# SensorBoard.net
KiCad netlist of a schematic drawn in EAGLE
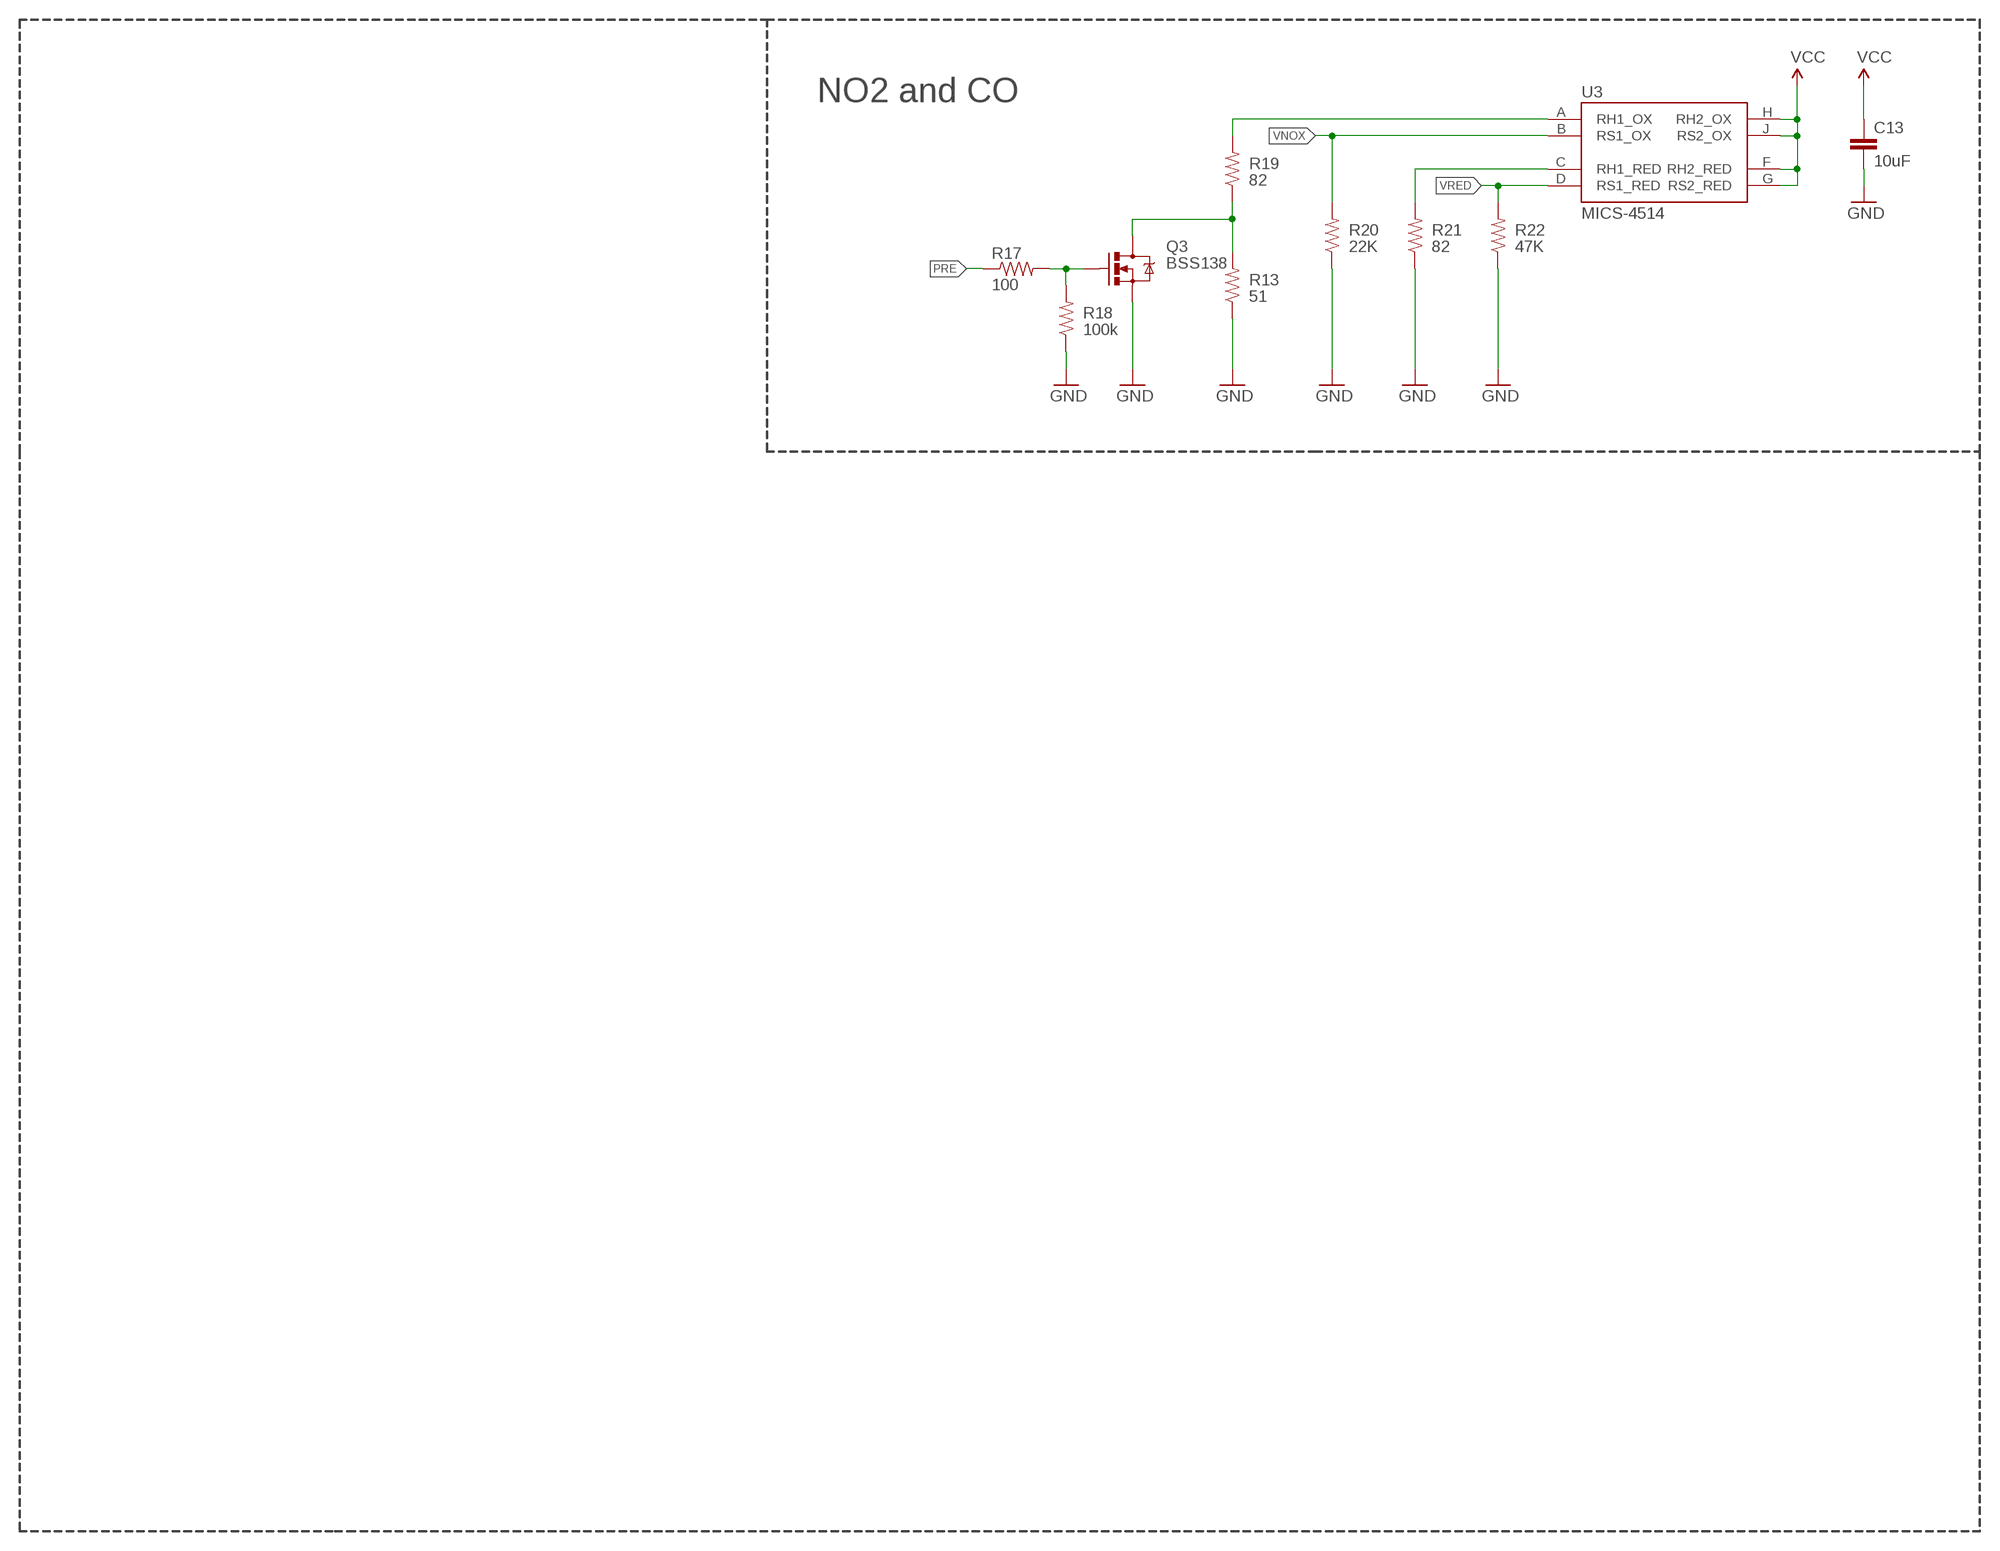
[diagram p0: schematic, sheet 1]

(export (version "E")
  (design (tool "Eeschema 10.0.6"))
  (components
    (comp (ref "C13")
      (value "10uF")
      (footprint "eagle-import:1206")
      (libsource (lib "eagle-import") (part "CAP1206"))
    )
    (comp (ref "Q3")
      (value "MOSFET-NCHANNELBSS138")
      (footprint "eagle-import:SOT23-3")
      (fields (field (name "P_NAME") "BSS138"))
      (libsource (lib "eagle-import") (part "MOSFET-NCHANNELBSS138"))
    )
    (comp (ref "R13")
      (value "51")
      (footprint "eagle-import:1206")
      (libsource (lib "eagle-import") (part "RESISTOR1206"))
    )
    (comp (ref "R17")
      (value "100")
      (footprint "eagle-import:0603-RES")
      (libsource (lib "eagle-import") (part "100OHM1/10W1%(0603)"))
    )
    (comp (ref "R18")
      (value "100k")
      (footprint "eagle-import:0603-RES")
      (libsource (lib "eagle-import") (part "100KOHM1/10W1%(0603)"))
    )
    (comp (ref "R19")
      (value "82")
      (footprint "eagle-import:1206")
      (libsource (lib "eagle-import") (part "RESISTOR1206"))
    )
    (comp (ref "R20")
      (value "22K")
      (footprint "eagle-import:0603-RES")
      (libsource (lib "eagle-import") (part "22KOHM1/10W1%(0603)"))
    )
    (comp (ref "R21")
      (value "82")
      (footprint "eagle-import:1206")
      (libsource (lib "eagle-import") (part "RESISTOR1206"))
    )
    (comp (ref "R22")
      (value "47K")
      (footprint "eagle-import:0603-RES")
      (libsource (lib "eagle-import") (part "47KOHM1/10W1%(0603)"))
    )
    (comp (ref "U3")
      (value "MICS-4514")
      (footprint "eagle-import:MICS_10-SMD")
      (libsource (lib "eagle-import") (part "MICS-4514"))
    )
  )
  (nets
    (net (code "1") (name "GND") (class "Default")
      (node (ref "C13") (pin "2") (pinfunction "2_2") (pintype "passive"))
      (node (ref "Q3") (pin "2") (pinfunction "S_2") (pintype "passive"))
      (node (ref "R13") (pin "1") (pinfunction "1_1") (pintype "passive"))
      (node (ref "R18") (pin "1") (pinfunction "1_1") (pintype "passive"))
      (node (ref "R20") (pin "1") (pinfunction "1_1") (pintype "passive"))
      (node (ref "R21") (pin "1") (pinfunction "1_1") (pintype "passive"))
      (node (ref "R22") (pin "1") (pinfunction "1_1") (pintype "passive"))
    )
    (net (code "2") (name "Net-(Q3-D)") (class "Default")
      (node (ref "Q3") (pin "3") (pinfunction "D_3") (pintype "passive"))
      (node (ref "R13") (pin "2") (pinfunction "2_2") (pintype "passive"))
      (node (ref "R19") (pin "1") (pinfunction "1_1") (pintype "passive"))
    )
    (net (code "3") (name "Net-(Q3-G)") (class "Default")
      (node (ref "Q3") (pin "1") (pinfunction "G_1") (pintype "passive"))
      (node (ref "R17") (pin "2") (pinfunction "2_2") (pintype "passive"))
      (node (ref "R18") (pin "2") (pinfunction "2_2") (pintype "passive"))
    )
    (net (code "4") (name "Net-(U3-RH1_OX)") (class "Default")
      (node (ref "R19") (pin "2") (pinfunction "2_2") (pintype "passive"))
      (node (ref "U3") (pin "A") (pinfunction "RH1_OX_A") (pintype "bidirectional"))
    )
    (net (code "5") (name "Net-(U3-RH1_RED)") (class "Default")
      (node (ref "R21") (pin "2") (pinfunction "2_2") (pintype "passive"))
      (node (ref "U3") (pin "C") (pinfunction "RH1_RED_C") (pintype "bidirectional"))
    )
    (net (code "6") (name "PRE") (class "Default")
      (node (ref "R17") (pin "1") (pinfunction "1_1") (pintype "passive"))
    )
    (net (code "7") (name "VCC") (class "Default")
      (node (ref "C13") (pin "1") (pinfunction "1_1") (pintype "passive"))
      (node (ref "U3") (pin "F") (pinfunction "RH2_RED_F") (pintype "bidirectional"))
      (node (ref "U3") (pin "G") (pinfunction "RS2_RED_G") (pintype "bidirectional"))
      (node (ref "U3") (pin "H") (pinfunction "RH2_OX_H") (pintype "bidirectional"))
      (node (ref "U3") (pin "J") (pinfunction "RS2_OX_J") (pintype "bidirectional"))
    )
    (net (code "8") (name "VNOX") (class "Default")
      (node (ref "R20") (pin "2") (pinfunction "2_2") (pintype "passive"))
      (node (ref "U3") (pin "B") (pinfunction "RS1_OX_B") (pintype "bidirectional"))
    )
    (net (code "9") (name "VRED") (class "Default")
      (node (ref "R22") (pin "2") (pinfunction "2_2") (pintype "passive"))
      (node (ref "U3") (pin "D") (pinfunction "RS1_RED_D") (pintype "bidirectional"))
    )
  )
)
